# LED.net
KiCad netlist of a schematic drawn in Altium Designer
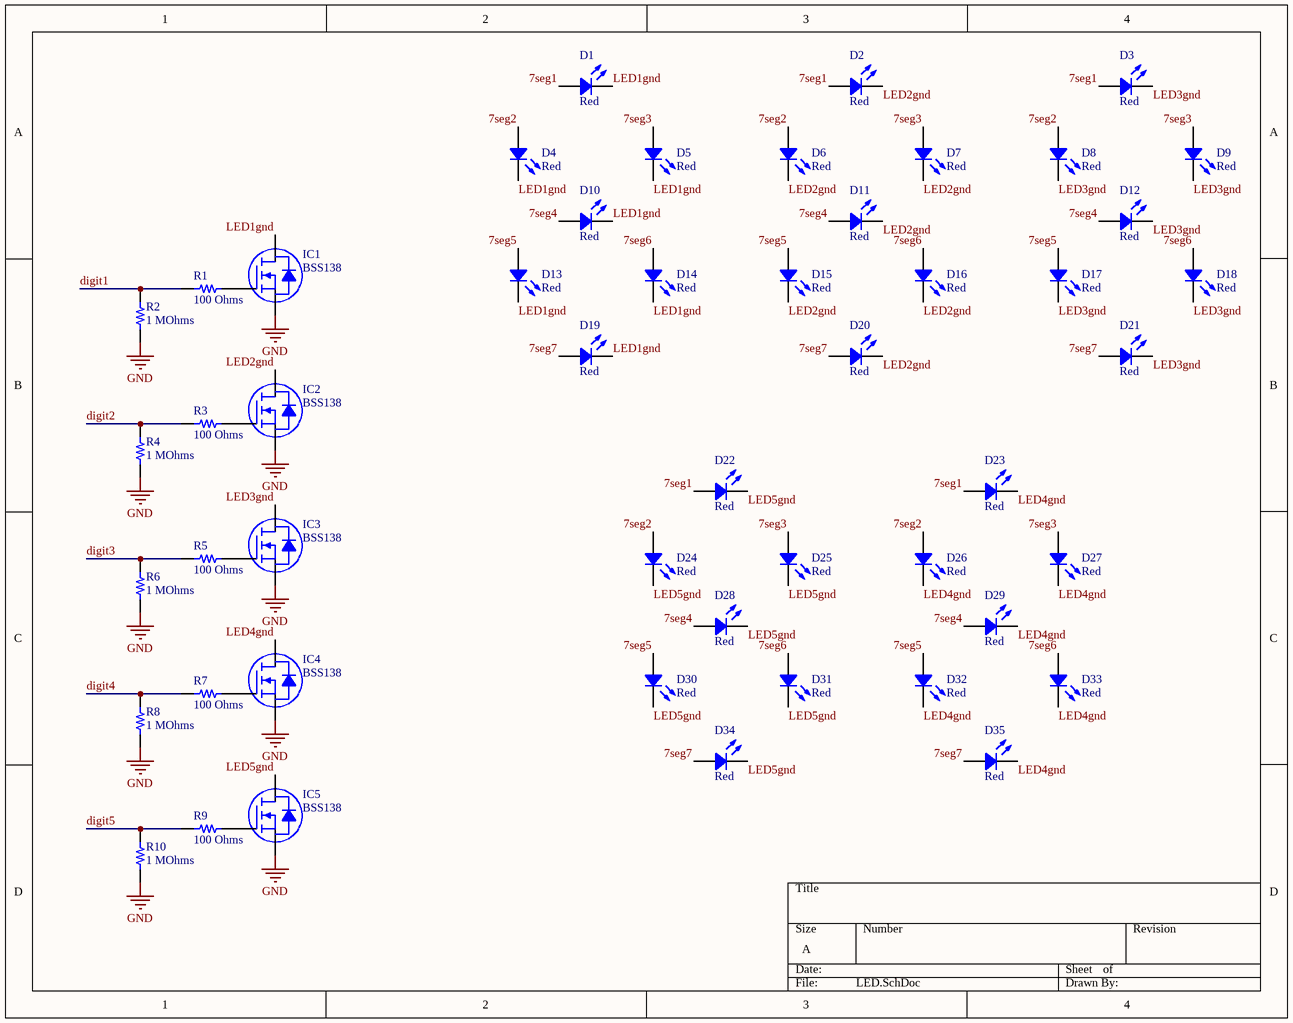
[diagram p0: LED.SchDoc]

(export (version "E")
  (design (tool "Eeschema 10.0.6"))
  (components
    (comp (ref "D1")
      (value "Red")
      (footprint "LED 0805_2012 RED")
      (description "LED RED DIFFUSED SMD")
      (fields
        (field (name "PART NUMBER") "SML-LXT0805SRW-TR")
        (field (name "MANUFACTURER") "Lumex Opto/Components Inc.")
      )
      (libsource (lib "Celestial Altium Library - altium_library") (part "LED"))
    )
    (comp (ref "D2")
      (value "Red")
      (footprint "LED 0805_2012 RED")
      (description "LED RED DIFFUSED SMD")
      (fields
        (field (name "PART NUMBER") "SML-LXT0805SRW-TR")
        (field (name "MANUFACTURER") "Lumex Opto/Components Inc.")
      )
      (libsource (lib "Celestial Altium Library - altium_library") (part "LED"))
    )
    (comp (ref "D3")
      (value "Red")
      (footprint "LED 0805_2012 RED")
      (description "LED RED DIFFUSED SMD")
      (fields
        (field (name "PART NUMBER") "SML-LXT0805SRW-TR")
        (field (name "MANUFACTURER") "Lumex Opto/Components Inc.")
      )
      (libsource (lib "Celestial Altium Library - altium_library") (part "LED"))
    )
    (comp (ref "D4")
      (value "Red")
      (footprint "LED 0805_2012 RED")
      (description "LED RED DIFFUSED SMD")
      (fields
        (field (name "PART NUMBER") "SML-LXT0805SRW-TR")
        (field (name "MANUFACTURER") "Lumex Opto/Components Inc.")
      )
      (libsource (lib "Celestial Altium Library - altium_library") (part "LED"))
    )
    (comp (ref "D5")
      (value "Red")
      (footprint "LED 0805_2012 RED")
      (description "LED RED DIFFUSED SMD")
      (fields
        (field (name "PART NUMBER") "SML-LXT0805SRW-TR")
        (field (name "MANUFACTURER") "Lumex Opto/Components Inc.")
      )
      (libsource (lib "Celestial Altium Library - altium_library") (part "LED"))
    )
    (comp (ref "D6")
      (value "Red")
      (footprint "LED 0805_2012 RED")
      (description "LED RED DIFFUSED SMD")
      (fields
        (field (name "PART NUMBER") "SML-LXT0805SRW-TR")
        (field (name "MANUFACTURER") "Lumex Opto/Components Inc.")
      )
      (libsource (lib "Celestial Altium Library - altium_library") (part "LED"))
    )
    (comp (ref "D7")
      (value "Red")
      (footprint "LED 0805_2012 RED")
      (description "LED RED DIFFUSED SMD")
      (fields
        (field (name "PART NUMBER") "SML-LXT0805SRW-TR")
        (field (name "MANUFACTURER") "Lumex Opto/Components Inc.")
      )
      (libsource (lib "Celestial Altium Library - altium_library") (part "LED"))
    )
    (comp (ref "D8")
      (value "Red")
      (footprint "LED 0805_2012 RED")
      (description "LED RED DIFFUSED SMD")
      (fields
        (field (name "PART NUMBER") "SML-LXT0805SRW-TR")
        (field (name "MANUFACTURER") "Lumex Opto/Components Inc.")
      )
      (libsource (lib "Celestial Altium Library - altium_library") (part "LED"))
    )
    (comp (ref "D9")
      (value "Red")
      (footprint "LED 0805_2012 RED")
      (description "LED RED DIFFUSED SMD")
      (fields
        (field (name "PART NUMBER") "SML-LXT0805SRW-TR")
        (field (name "MANUFACTURER") "Lumex Opto/Components Inc.")
      )
      (libsource (lib "Celestial Altium Library - altium_library") (part "LED"))
    )
    (comp (ref "D10")
      (value "Red")
      (footprint "LED 0805_2012 RED")
      (description "LED RED DIFFUSED SMD")
      (fields
        (field (name "PART NUMBER") "SML-LXT0805SRW-TR")
        (field (name "MANUFACTURER") "Lumex Opto/Components Inc.")
      )
      (libsource (lib "Celestial Altium Library - altium_library") (part "LED"))
    )
    (comp (ref "D11")
      (value "Red")
      (footprint "LED 0805_2012 RED")
      (description "LED RED DIFFUSED SMD")
      (fields
        (field (name "PART NUMBER") "SML-LXT0805SRW-TR")
        (field (name "MANUFACTURER") "Lumex Opto/Components Inc.")
      )
      (libsource (lib "Celestial Altium Library - altium_library") (part "LED"))
    )
    (comp (ref "D12")
      (value "Red")
      (footprint "LED 0805_2012 RED")
      (description "LED RED DIFFUSED SMD")
      (fields
        (field (name "PART NUMBER") "SML-LXT0805SRW-TR")
        (field (name "MANUFACTURER") "Lumex Opto/Components Inc.")
      )
      (libsource (lib "Celestial Altium Library - altium_library") (part "LED"))
    )
    (comp (ref "D13")
      (value "Red")
      (footprint "LED 0805_2012 RED")
      (description "LED RED DIFFUSED SMD")
      (fields
        (field (name "PART NUMBER") "SML-LXT0805SRW-TR")
        (field (name "MANUFACTURER") "Lumex Opto/Components Inc.")
      )
      (libsource (lib "Celestial Altium Library - altium_library") (part "LED"))
    )
    (comp (ref "D14")
      (value "Red")
      (footprint "LED 0805_2012 RED")
      (description "LED RED DIFFUSED SMD")
      (fields
        (field (name "PART NUMBER") "SML-LXT0805SRW-TR")
        (field (name "MANUFACTURER") "Lumex Opto/Components Inc.")
      )
      (libsource (lib "Celestial Altium Library - altium_library") (part "LED"))
    )
    (comp (ref "D15")
      (value "Red")
      (footprint "LED 0805_2012 RED")
      (description "LED RED DIFFUSED SMD")
      (fields
        (field (name "PART NUMBER") "SML-LXT0805SRW-TR")
        (field (name "MANUFACTURER") "Lumex Opto/Components Inc.")
      )
      (libsource (lib "Celestial Altium Library - altium_library") (part "LED"))
    )
    (comp (ref "D16")
      (value "Red")
      (footprint "LED 0805_2012 RED")
      (description "LED RED DIFFUSED SMD")
      (fields
        (field (name "PART NUMBER") "SML-LXT0805SRW-TR")
        (field (name "MANUFACTURER") "Lumex Opto/Components Inc.")
      )
      (libsource (lib "Celestial Altium Library - altium_library") (part "LED"))
    )
    (comp (ref "D17")
      (value "Red")
      (footprint "LED 0805_2012 RED")
      (description "LED RED DIFFUSED SMD")
      (fields
        (field (name "PART NUMBER") "SML-LXT0805SRW-TR")
        (field (name "MANUFACTURER") "Lumex Opto/Components Inc.")
      )
      (libsource (lib "Celestial Altium Library - altium_library") (part "LED"))
    )
    (comp (ref "D18")
      (value "Red")
      (footprint "LED 0805_2012 RED")
      (description "LED RED DIFFUSED SMD")
      (fields
        (field (name "PART NUMBER") "SML-LXT0805SRW-TR")
        (field (name "MANUFACTURER") "Lumex Opto/Components Inc.")
      )
      (libsource (lib "Celestial Altium Library - altium_library") (part "LED"))
    )
    (comp (ref "D19")
      (value "Red")
      (footprint "LED 0805_2012 RED")
      (description "LED RED DIFFUSED SMD")
      (fields
        (field (name "PART NUMBER") "SML-LXT0805SRW-TR")
        (field (name "MANUFACTURER") "Lumex Opto/Components Inc.")
      )
      (libsource (lib "Celestial Altium Library - altium_library") (part "LED"))
    )
    (comp (ref "D20")
      (value "Red")
      (footprint "LED 0805_2012 RED")
      (description "LED RED DIFFUSED SMD")
      (fields
        (field (name "PART NUMBER") "SML-LXT0805SRW-TR")
        (field (name "MANUFACTURER") "Lumex Opto/Components Inc.")
      )
      (libsource (lib "Celestial Altium Library - altium_library") (part "LED"))
    )
    (comp (ref "D21")
      (value "Red")
      (footprint "LED 0805_2012 RED")
      (description "LED RED DIFFUSED SMD")
      (fields
        (field (name "PART NUMBER") "SML-LXT0805SRW-TR")
        (field (name "MANUFACTURER") "Lumex Opto/Components Inc.")
      )
      (libsource (lib "Celestial Altium Library - altium_library") (part "LED"))
    )
    (comp (ref "D22")
      (value "Red")
      (footprint "LED 0805_2012 RED")
      (description "LED RED DIFFUSED SMD")
      (fields
        (field (name "PART NUMBER") "SML-LXT0805SRW-TR")
        (field (name "MANUFACTURER") "Lumex Opto/Components Inc.")
      )
      (libsource (lib "Celestial Altium Library - altium_library") (part "LED"))
    )
    (comp (ref "D23")
      (value "Red")
      (footprint "LED 0805_2012 RED")
      (description "LED RED DIFFUSED SMD")
      (fields
        (field (name "PART NUMBER") "SML-LXT0805SRW-TR")
        (field (name "MANUFACTURER") "Lumex Opto/Components Inc.")
      )
      (libsource (lib "Celestial Altium Library - altium_library") (part "LED"))
    )
    (comp (ref "D24")
      (value "Red")
      (footprint "LED 0805_2012 RED")
      (description "LED RED DIFFUSED SMD")
      (fields
        (field (name "PART NUMBER") "SML-LXT0805SRW-TR")
        (field (name "MANUFACTURER") "Lumex Opto/Components Inc.")
      )
      (libsource (lib "Celestial Altium Library - altium_library") (part "LED"))
    )
    (comp (ref "D25")
      (value "Red")
      (footprint "LED 0805_2012 RED")
      (description "LED RED DIFFUSED SMD")
      (fields
        (field (name "PART NUMBER") "SML-LXT0805SRW-TR")
        (field (name "MANUFACTURER") "Lumex Opto/Components Inc.")
      )
      (libsource (lib "Celestial Altium Library - altium_library") (part "LED"))
    )
    (comp (ref "D26")
      (value "Red")
      (footprint "LED 0805_2012 RED")
      (description "LED RED DIFFUSED SMD")
      (fields
        (field (name "PART NUMBER") "SML-LXT0805SRW-TR")
        (field (name "MANUFACTURER") "Lumex Opto/Components Inc.")
      )
      (libsource (lib "Celestial Altium Library - altium_library") (part "LED"))
    )
    (comp (ref "D27")
      (value "Red")
      (footprint "LED 0805_2012 RED")
      (description "LED RED DIFFUSED SMD")
      (fields
        (field (name "PART NUMBER") "SML-LXT0805SRW-TR")
        (field (name "MANUFACTURER") "Lumex Opto/Components Inc.")
      )
      (libsource (lib "Celestial Altium Library - altium_library") (part "LED"))
    )
    (comp (ref "D28")
      (value "Red")
      (footprint "LED 0805_2012 RED")
      (description "LED RED DIFFUSED SMD")
      (fields
        (field (name "PART NUMBER") "SML-LXT0805SRW-TR")
        (field (name "MANUFACTURER") "Lumex Opto/Components Inc.")
      )
      (libsource (lib "Celestial Altium Library - altium_library") (part "LED"))
    )
    (comp (ref "D29")
      (value "Red")
      (footprint "LED 0805_2012 RED")
      (description "LED RED DIFFUSED SMD")
      (fields
        (field (name "PART NUMBER") "SML-LXT0805SRW-TR")
        (field (name "MANUFACTURER") "Lumex Opto/Components Inc.")
      )
      (libsource (lib "Celestial Altium Library - altium_library") (part "LED"))
    )
    (comp (ref "D30")
      (value "Red")
      (footprint "LED 0805_2012 RED")
      (description "LED RED DIFFUSED SMD")
      (fields
        (field (name "PART NUMBER") "SML-LXT0805SRW-TR")
        (field (name "MANUFACTURER") "Lumex Opto/Components Inc.")
      )
      (libsource (lib "Celestial Altium Library - altium_library") (part "LED"))
    )
    (comp (ref "D31")
      (value "Red")
      (footprint "LED 0805_2012 RED")
      (description "LED RED DIFFUSED SMD")
      (fields
        (field (name "PART NUMBER") "SML-LXT0805SRW-TR")
        (field (name "MANUFACTURER") "Lumex Opto/Components Inc.")
      )
      (libsource (lib "Celestial Altium Library - altium_library") (part "LED"))
    )
    (comp (ref "D32")
      (value "Red")
      (footprint "LED 0805_2012 RED")
      (description "LED RED DIFFUSED SMD")
      (fields
        (field (name "PART NUMBER") "SML-LXT0805SRW-TR")
        (field (name "MANUFACTURER") "Lumex Opto/Components Inc.")
      )
      (libsource (lib "Celestial Altium Library - altium_library") (part "LED"))
    )
    (comp (ref "D33")
      (value "Red")
      (footprint "LED 0805_2012 RED")
      (description "LED RED DIFFUSED SMD")
      (fields
        (field (name "PART NUMBER") "SML-LXT0805SRW-TR")
        (field (name "MANUFACTURER") "Lumex Opto/Components Inc.")
      )
      (libsource (lib "Celestial Altium Library - altium_library") (part "LED"))
    )
    (comp (ref "D34")
      (value "Red")
      (footprint "LED 0805_2012 RED")
      (description "LED RED DIFFUSED SMD")
      (fields
        (field (name "PART NUMBER") "SML-LXT0805SRW-TR")
        (field (name "MANUFACTURER") "Lumex Opto/Components Inc.")
      )
      (libsource (lib "Celestial Altium Library - altium_library") (part "LED"))
    )
    (comp (ref "D35")
      (value "Red")
      (footprint "LED 0805_2012 RED")
      (description "LED RED DIFFUSED SMD")
      (fields
        (field (name "PART NUMBER") "SML-LXT0805SRW-TR")
        (field (name "MANUFACTURER") "Lumex Opto/Components Inc.")
      )
      (libsource (lib "Celestial Altium Library - altium_library") (part "LED"))
    )
    (comp (ref "IC1")
      (value "BSS138")
      (footprint "ON SEMI SOT-23-3")
      (description "MOSFET N-CH 50V 220MA SOT-23")
      (fields (field (name "MANUFACTURER") "ON Semiconductor"))
      (libsource (lib "Celestial Altium Library - altium_library") (part "ON SEMI MOSFET N-CH SOT-23-3"))
    )
    (comp (ref "IC2")
      (value "BSS138")
      (footprint "ON SEMI SOT-23-3")
      (description "MOSFET N-CH 50V 220MA SOT-23")
      (fields (field (name "MANUFACTURER") "ON Semiconductor"))
      (libsource (lib "Celestial Altium Library - altium_library") (part "ON SEMI MOSFET N-CH SOT-23-3"))
    )
    (comp (ref "IC3")
      (value "BSS138")
      (footprint "ON SEMI SOT-23-3")
      (description "MOSFET N-CH 50V 220MA SOT-23")
      (fields (field (name "MANUFACTURER") "ON Semiconductor"))
      (libsource (lib "Celestial Altium Library - altium_library") (part "ON SEMI MOSFET N-CH SOT-23-3"))
    )
    (comp (ref "IC4")
      (value "BSS138")
      (footprint "ON SEMI SOT-23-3")
      (description "MOSFET N-CH 50V 220MA SOT-23")
      (fields (field (name "MANUFACTURER") "ON Semiconductor"))
      (libsource (lib "Celestial Altium Library - altium_library") (part "ON SEMI MOSFET N-CH SOT-23-3"))
    )
    (comp (ref "IC5")
      (value "BSS138")
      (footprint "ON SEMI SOT-23-3")
      (description "MOSFET N-CH 50V 220MA SOT-23")
      (fields (field (name "MANUFACTURER") "ON Semiconductor"))
      (libsource (lib "Celestial Altium Library - altium_library") (part "ON SEMI MOSFET N-CH SOT-23-3"))
    )
    (comp (ref "R1")
      (value "100 Ohms")
      (footprint "RES 0805_2012")
      (description "RES SMD 100 OHM 1% 0.4W 0805")
      (fields (field (name "PART NUMBER") "RCS0805100RFKEA") (field (name "MANUFACTURER") "Vishay Dale"))
      (libsource (lib "Celestial Altium Library - altium_library") (part "Resistor"))
    )
    (comp (ref "R2")
      (value "1 MOhms")
      (footprint "RES 0805_2012")
      (description "RES 1M OHM 0.1% 1/8W 0805")
      (fields
        (field (name "PART NUMBER") "ERA-6AEB105V")
        (field (name "MANUFACTURER") "Panasonic Electronic Components")
      )
      (libsource (lib "Celestial Altium Library - altium_library") (part "Resistor"))
    )
    (comp (ref "R3")
      (value "100 Ohms")
      (footprint "RES 0805_2012")
      (description "RES SMD 100 OHM 1% 0.4W 0805")
      (fields (field (name "PART NUMBER") "RCS0805100RFKEA") (field (name "MANUFACTURER") "Vishay Dale"))
      (libsource (lib "Celestial Altium Library - altium_library") (part "Resistor"))
    )
    (comp (ref "R4")
      (value "1 MOhms")
      (footprint "RES 0805_2012")
      (description "RES 1M OHM 0.1% 1/8W 0805")
      (fields
        (field (name "PART NUMBER") "ERA-6AEB105V")
        (field (name "MANUFACTURER") "Panasonic Electronic Components")
      )
      (libsource (lib "Celestial Altium Library - altium_library") (part "Resistor"))
    )
    (comp (ref "R5")
      (value "100 Ohms")
      (footprint "RES 0805_2012")
      (description "RES SMD 100 OHM 1% 0.4W 0805")
      (fields (field (name "PART NUMBER") "RCS0805100RFKEA") (field (name "MANUFACTURER") "Vishay Dale"))
      (libsource (lib "Celestial Altium Library - altium_library") (part "Resistor"))
    )
    (comp (ref "R6")
      (value "1 MOhms")
      (footprint "RES 0805_2012")
      (description "RES 1M OHM 0.1% 1/8W 0805")
      (fields
        (field (name "PART NUMBER") "ERA-6AEB105V")
        (field (name "MANUFACTURER") "Panasonic Electronic Components")
      )
      (libsource (lib "Celestial Altium Library - altium_library") (part "Resistor"))
    )
    (comp (ref "R7")
      (value "100 Ohms")
      (footprint "RES 0805_2012")
      (description "RES SMD 100 OHM 1% 0.4W 0805")
      (fields (field (name "PART NUMBER") "RCS0805100RFKEA") (field (name "MANUFACTURER") "Vishay Dale"))
      (libsource (lib "Celestial Altium Library - altium_library") (part "Resistor"))
    )
    (comp (ref "R8")
      (value "1 MOhms")
      (footprint "RES 0805_2012")
      (description "RES 1M OHM 0.1% 1/8W 0805")
      (fields
        (field (name "PART NUMBER") "ERA-6AEB105V")
        (field (name "MANUFACTURER") "Panasonic Electronic Components")
      )
      (libsource (lib "Celestial Altium Library - altium_library") (part "Resistor"))
    )
    (comp (ref "R9")
      (value "100 Ohms")
      (footprint "RES 0805_2012")
      (description "RES SMD 100 OHM 1% 0.4W 0805")
      (fields (field (name "PART NUMBER") "RCS0805100RFKEA") (field (name "MANUFACTURER") "Vishay Dale"))
      (libsource (lib "Celestial Altium Library - altium_library") (part "Resistor"))
    )
    (comp (ref "R10")
      (value "1 MOhms")
      (footprint "RES 0805_2012")
      (description "RES 1M OHM 0.1% 1/8W 0805")
      (fields
        (field (name "PART NUMBER") "ERA-6AEB105V")
        (field (name "MANUFACTURER") "Panasonic Electronic Components")
      )
      (libsource (lib "Celestial Altium Library - altium_library") (part "Resistor"))
    )
  )
  (nets
    (net (code "1") (name "/7seg1") (class "Default")
      (node (ref "D1") (pin "1") (pinfunction "1_1") (pintype "passive"))
      (node (ref "D2") (pin "1") (pinfunction "1_1") (pintype "passive"))
      (node (ref "D22") (pin "1") (pinfunction "1_1") (pintype "passive"))
      (node (ref "D23") (pin "1") (pinfunction "1_1") (pintype "passive"))
      (node (ref "D3") (pin "1") (pinfunction "1_1") (pintype "passive"))
    )
    (net (code "2") (name "/7seg2") (class "Default")
      (node (ref "D24") (pin "1") (pinfunction "1_1") (pintype "passive"))
      (node (ref "D26") (pin "1") (pinfunction "1_1") (pintype "passive"))
      (node (ref "D4") (pin "1") (pinfunction "1_1") (pintype "passive"))
      (node (ref "D6") (pin "1") (pinfunction "1_1") (pintype "passive"))
      (node (ref "D8") (pin "1") (pinfunction "1_1") (pintype "passive"))
    )
    (net (code "3") (name "/7seg3") (class "Default")
      (node (ref "D25") (pin "1") (pinfunction "1_1") (pintype "passive"))
      (node (ref "D27") (pin "1") (pinfunction "1_1") (pintype "passive"))
      (node (ref "D5") (pin "1") (pinfunction "1_1") (pintype "passive"))
      (node (ref "D7") (pin "1") (pinfunction "1_1") (pintype "passive"))
      (node (ref "D9") (pin "1") (pinfunction "1_1") (pintype "passive"))
    )
    (net (code "4") (name "/7seg4") (class "Default")
      (node (ref "D10") (pin "1") (pinfunction "1_1") (pintype "passive"))
      (node (ref "D11") (pin "1") (pinfunction "1_1") (pintype "passive"))
      (node (ref "D12") (pin "1") (pinfunction "1_1") (pintype "passive"))
      (node (ref "D28") (pin "1") (pinfunction "1_1") (pintype "passive"))
      (node (ref "D29") (pin "1") (pinfunction "1_1") (pintype "passive"))
    )
    (net (code "5") (name "/7seg5") (class "Default")
      (node (ref "D13") (pin "1") (pinfunction "1_1") (pintype "passive"))
      (node (ref "D15") (pin "1") (pinfunction "1_1") (pintype "passive"))
      (node (ref "D17") (pin "1") (pinfunction "1_1") (pintype "passive"))
      (node (ref "D30") (pin "1") (pinfunction "1_1") (pintype "passive"))
      (node (ref "D32") (pin "1") (pinfunction "1_1") (pintype "passive"))
    )
    (net (code "6") (name "/7seg6") (class "Default")
      (node (ref "D14") (pin "1") (pinfunction "1_1") (pintype "passive"))
      (node (ref "D16") (pin "1") (pinfunction "1_1") (pintype "passive"))
      (node (ref "D18") (pin "1") (pinfunction "1_1") (pintype "passive"))
      (node (ref "D31") (pin "1") (pinfunction "1_1") (pintype "passive"))
      (node (ref "D33") (pin "1") (pinfunction "1_1") (pintype "passive"))
    )
    (net (code "7") (name "/7seg7") (class "Default")
      (node (ref "D19") (pin "1") (pinfunction "1_1") (pintype "passive"))
      (node (ref "D20") (pin "1") (pinfunction "1_1") (pintype "passive"))
      (node (ref "D21") (pin "1") (pinfunction "1_1") (pintype "passive"))
      (node (ref "D34") (pin "1") (pinfunction "1_1") (pintype "passive"))
      (node (ref "D35") (pin "1") (pinfunction "1_1") (pintype "passive"))
    )
    (net (code "8") (name "/LED1gnd") (class "Default")
      (node (ref "D1") (pin "2") (pinfunction "2_2") (pintype "passive"))
      (node (ref "D10") (pin "2") (pinfunction "2_2") (pintype "passive"))
      (node (ref "D13") (pin "2") (pinfunction "2_2") (pintype "passive"))
      (node (ref "D14") (pin "2") (pinfunction "2_2") (pintype "passive"))
      (node (ref "D19") (pin "2") (pinfunction "2_2") (pintype "passive"))
      (node (ref "D4") (pin "2") (pinfunction "2_2") (pintype "passive"))
      (node (ref "D5") (pin "2") (pinfunction "2_2") (pintype "passive"))
      (node (ref "IC1") (pin "3") (pinfunction "D_3") (pintype "passive"))
    )
    (net (code "9") (name "/LED2gnd") (class "Default")
      (node (ref "D11") (pin "2") (pinfunction "2_2") (pintype "passive"))
      (node (ref "D15") (pin "2") (pinfunction "2_2") (pintype "passive"))
      (node (ref "D16") (pin "2") (pinfunction "2_2") (pintype "passive"))
      (node (ref "D2") (pin "2") (pinfunction "2_2") (pintype "passive"))
      (node (ref "D20") (pin "2") (pinfunction "2_2") (pintype "passive"))
      (node (ref "D6") (pin "2") (pinfunction "2_2") (pintype "passive"))
      (node (ref "D7") (pin "2") (pinfunction "2_2") (pintype "passive"))
      (node (ref "IC2") (pin "3") (pinfunction "D_3") (pintype "passive"))
    )
    (net (code "10") (name "/LED3gnd") (class "Default")
      (node (ref "D12") (pin "2") (pinfunction "2_2") (pintype "passive"))
      (node (ref "D17") (pin "2") (pinfunction "2_2") (pintype "passive"))
      (node (ref "D18") (pin "2") (pinfunction "2_2") (pintype "passive"))
      (node (ref "D21") (pin "2") (pinfunction "2_2") (pintype "passive"))
      (node (ref "D3") (pin "2") (pinfunction "2_2") (pintype "passive"))
      (node (ref "D8") (pin "2") (pinfunction "2_2") (pintype "passive"))
      (node (ref "D9") (pin "2") (pinfunction "2_2") (pintype "passive"))
      (node (ref "IC3") (pin "3") (pinfunction "D_3") (pintype "passive"))
    )
    (net (code "11") (name "/LED4gnd") (class "Default")
      (node (ref "D23") (pin "2") (pinfunction "2_2") (pintype "passive"))
      (node (ref "D26") (pin "2") (pinfunction "2_2") (pintype "passive"))
      (node (ref "D27") (pin "2") (pinfunction "2_2") (pintype "passive"))
      (node (ref "D29") (pin "2") (pinfunction "2_2") (pintype "passive"))
      (node (ref "D32") (pin "2") (pinfunction "2_2") (pintype "passive"))
      (node (ref "D33") (pin "2") (pinfunction "2_2") (pintype "passive"))
      (node (ref "D35") (pin "2") (pinfunction "2_2") (pintype "passive"))
      (node (ref "IC4") (pin "3") (pinfunction "D_3") (pintype "passive"))
    )
    (net (code "12") (name "/LED5gnd") (class "Default")
      (node (ref "D22") (pin "2") (pinfunction "2_2") (pintype "passive"))
      (node (ref "D24") (pin "2") (pinfunction "2_2") (pintype "passive"))
      (node (ref "D25") (pin "2") (pinfunction "2_2") (pintype "passive"))
      (node (ref "D28") (pin "2") (pinfunction "2_2") (pintype "passive"))
      (node (ref "D30") (pin "2") (pinfunction "2_2") (pintype "passive"))
      (node (ref "D31") (pin "2") (pinfunction "2_2") (pintype "passive"))
      (node (ref "D34") (pin "2") (pinfunction "2_2") (pintype "passive"))
      (node (ref "IC5") (pin "3") (pinfunction "D_3") (pintype "passive"))
    )
    (net (code "13") (name "/digit1") (class "Default")
      (node (ref "R1") (pin "1") (pinfunction "1_1") (pintype "passive"))
      (node (ref "R2") (pin "2") (pinfunction "2_2") (pintype "passive"))
    )
    (net (code "14") (name "/digit2") (class "Default")
      (node (ref "R3") (pin "1") (pinfunction "1_1") (pintype "passive"))
      (node (ref "R4") (pin "2") (pinfunction "2_2") (pintype "passive"))
    )
    (net (code "15") (name "/digit3") (class "Default")
      (node (ref "R5") (pin "1") (pinfunction "1_1") (pintype "passive"))
      (node (ref "R6") (pin "2") (pinfunction "2_2") (pintype "passive"))
    )
    (net (code "16") (name "/digit4") (class "Default")
      (node (ref "R7") (pin "1") (pinfunction "1_1") (pintype "passive"))
      (node (ref "R8") (pin "2") (pinfunction "2_2") (pintype "passive"))
    )
    (net (code "17") (name "/digit5") (class "Default")
      (node (ref "R10") (pin "2") (pinfunction "2_2") (pintype "passive"))
      (node (ref "R9") (pin "1") (pinfunction "1_1") (pintype "passive"))
    )
    (net (code "18") (name "GND") (class "Default")
      (node (ref "IC1") (pin "2") (pinfunction "S_2") (pintype "passive"))
      (node (ref "IC2") (pin "2") (pinfunction "S_2") (pintype "passive"))
      (node (ref "IC3") (pin "2") (pinfunction "S_2") (pintype "passive"))
      (node (ref "IC4") (pin "2") (pinfunction "S_2") (pintype "passive"))
      (node (ref "IC5") (pin "2") (pinfunction "S_2") (pintype "passive"))
      (node (ref "R10") (pin "1") (pinfunction "1_1") (pintype "passive"))
      (node (ref "R2") (pin "1") (pinfunction "1_1") (pintype "passive"))
      (node (ref "R4") (pin "1") (pinfunction "1_1") (pintype "passive"))
      (node (ref "R6") (pin "1") (pinfunction "1_1") (pintype "passive"))
      (node (ref "R8") (pin "1") (pinfunction "1_1") (pintype "passive"))
    )
    (net (code "19") (name "Net-(IC1-G)") (class "Default")
      (node (ref "IC1") (pin "1") (pinfunction "G_1") (pintype "passive"))
      (node (ref "R1") (pin "2") (pinfunction "2_2") (pintype "passive"))
    )
    (net (code "20") (name "Net-(IC2-G)") (class "Default")
      (node (ref "IC2") (pin "1") (pinfunction "G_1") (pintype "passive"))
      (node (ref "R3") (pin "2") (pinfunction "2_2") (pintype "passive"))
    )
    (net (code "21") (name "Net-(IC3-G)") (class "Default")
      (node (ref "IC3") (pin "1") (pinfunction "G_1") (pintype "passive"))
      (node (ref "R5") (pin "2") (pinfunction "2_2") (pintype "passive"))
    )
    (net (code "22") (name "Net-(IC4-G)") (class "Default")
      (node (ref "IC4") (pin "1") (pinfunction "G_1") (pintype "passive"))
      (node (ref "R7") (pin "2") (pinfunction "2_2") (pintype "passive"))
    )
    (net (code "23") (name "Net-(IC5-G)") (class "Default")
      (node (ref "IC5") (pin "1") (pinfunction "G_1") (pintype "passive"))
      (node (ref "R9") (pin "2") (pinfunction "2_2") (pintype "passive"))
    )
  )
)
